# Skematik_FC.net
KiCad netlist of a schematic drawn in EAGLE
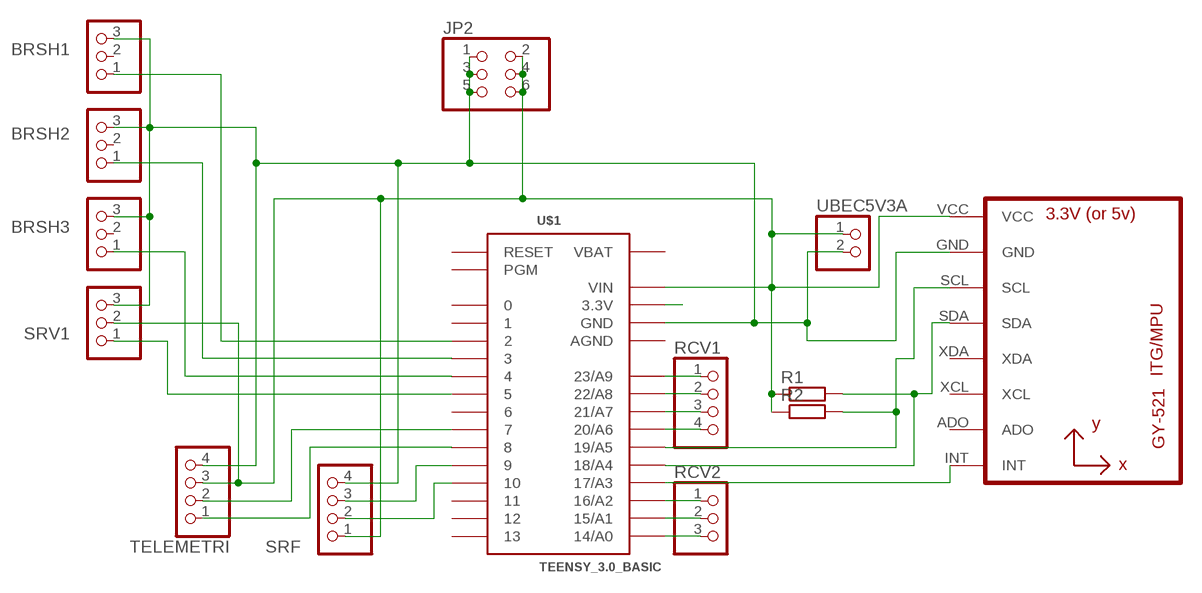
[diagram p0: schematic, sheet 1]

(export (version "E")
  (design (tool "Eeschema 10.0.6"))
  (components
    (comp (ref "BRSH1")
      (value "PINHD-1X3")
      (footprint "eagle-import:1X03")
      (libsource (lib "eagle-import") (part "PINHD-1X3"))
    )
    (comp (ref "BRSH3")
      (value "PINHD-1X3")
      (footprint "eagle-import:1X03")
      (libsource (lib "eagle-import") (part "PINHD-1X3"))
    )
    (comp (ref "BRSHL2")
      (value "BRSH2")
      (footprint "eagle-import:1X03")
      (libsource (lib "eagle-import") (part "PINHD-1X3"))
    )
    (comp (ref "JP2")
      (value "PINHD-2X3")
      (footprint "eagle-import:2X03")
      (libsource (lib "eagle-import") (part "PINHD-2X3"))
    )
    (comp (ref "R1")
      (value "R-EU_0207/7")
      (footprint "eagle-import:0207_7")
      (libsource (lib "eagle-import") (part "R-EU_0207/7"))
    )
    (comp (ref "R2")
      (value "R-EU_0207/7")
      (footprint "eagle-import:0207_7")
      (libsource (lib "eagle-import") (part "R-EU_0207/7"))
    )
    (comp (ref "RCV1")
      (value "PINHD-1X4")
      (footprint "eagle-import:1X04")
      (libsource (lib "eagle-import") (part "PINHD-1X4"))
    )
    (comp (ref "RCV2")
      (value "PINHD-1X3")
      (footprint "eagle-import:1X03")
      (libsource (lib "eagle-import") (part "PINHD-1X3"))
    )
    (comp (ref "SRF")
      (value "PINHD-1X4")
      (footprint "eagle-import:1X04")
      (libsource (lib "eagle-import") (part "PINHD-1X4"))
    )
    (comp (ref "SRV1")
      (value "PINHD-1X3")
      (footprint "eagle-import:1X03")
      (libsource (lib "eagle-import") (part "PINHD-1X3"))
    )
    (comp (ref "TELEMETRI")
      (value "PINHD-1X4")
      (footprint "eagle-import:1X04")
      (libsource (lib "eagle-import") (part "PINHD-1X4"))
    )
    (comp (ref "U$1")
      (value "TEENSY_3.0_BASIC")
      (footprint "eagle-import:TEENSY_3.0_BASIC")
      (libsource (lib "eagle-import") (part "TEENSY_3.0_BASIC"))
    )
    (comp (ref "U1")
      (value "GY-521MPU6050")
      (footprint "eagle-import:GY-521")
      (libsource (lib "eagle-import") (part "GY-521MPU6050"))
    )
    (comp (ref "UBEC5V3A")
      (value "PINHD-1X2")
      (footprint "eagle-import:1X02")
      (libsource (lib "eagle-import") (part "PINHD-1X2"))
    )
  )
  (nets
    (net (code "1") (name "/AGND") (class "Default")
      (node (ref "U$1") (pin "AGND") (pinfunction "AGND_AGND") (pintype "power_in"))
    )
    (net (code "2") (name "/VBAT") (class "Default")
      (node (ref "U$1") (pin "VBAT") (pinfunction "VBAT_VBAT") (pintype "power_in"))
    )
    (net (code "3") (name "Net-(BRSH1-Pad1)") (class "Default")
      (node (ref "BRSH1") (pin "1") (pinfunction "1_1") (pintype "passive"))
      (node (ref "U$1") (pin "2") (pinfunction "2_2") (pintype "bidirectional"))
    )
    (net (code "4") (name "Net-(BRSH1-Pad3)") (class "Default")
      (node (ref "BRSH1") (pin "3") (pinfunction "3_3") (pintype "passive"))
      (node (ref "BRSH3") (pin "3") (pinfunction "3_3") (pintype "passive"))
      (node (ref "BRSHL2") (pin "3") (pinfunction "3_3") (pintype "passive"))
      (node (ref "JP2") (pin "1") (pinfunction "1_1") (pintype "passive"))
      (node (ref "JP2") (pin "3") (pinfunction "3_3") (pintype "passive"))
      (node (ref "JP2") (pin "5") (pinfunction "5_5") (pintype "passive"))
      (node (ref "SRF") (pin "4") (pinfunction "4_4") (pintype "passive"))
      (node (ref "SRV1") (pin "3") (pinfunction "3_3") (pintype "passive"))
      (node (ref "TELEMETRI") (pin "4") (pinfunction "4_4") (pintype "passive"))
      (node (ref "U$1") (pin "GND") (pinfunction "GND_GND") (pintype "power_in"))
      (node (ref "U$1") (pin "GND1") (pinfunction "GND_GND1") (pintype "power_in"))
      (node (ref "U1") (pin "GND") (pinfunction "GND_GND") (pintype "bidirectional"))
      (node (ref "UBEC5V3A") (pin "2") (pinfunction "2_2") (pintype "passive"))
    )
    (net (code "5") (name "Net-(BRSH3-Pad1)") (class "Default")
      (node (ref "BRSH3") (pin "1") (pinfunction "1_1") (pintype "passive"))
      (node (ref "U$1") (pin "4") (pinfunction "4_4") (pintype "bidirectional"))
    )
    (net (code "6") (name "Net-(BRSHL2-Pad1)") (class "Default")
      (node (ref "BRSHL2") (pin "1") (pinfunction "1_1") (pintype "passive"))
      (node (ref "U$1") (pin "3") (pinfunction "3_3") (pintype "bidirectional"))
    )
    (net (code "7") (name "Net-(JP2-Pad2)") (class "Default")
      (node (ref "JP2") (pin "2") (pinfunction "2_2") (pintype "passive"))
      (node (ref "JP2") (pin "4") (pinfunction "4_4") (pintype "passive"))
      (node (ref "JP2") (pin "6") (pinfunction "6_6") (pintype "passive"))
      (node (ref "R1") (pin "1") (pinfunction "1_1") (pintype "passive"))
      (node (ref "R2") (pin "1") (pinfunction "1_1") (pintype "passive"))
      (node (ref "SRF") (pin "1") (pinfunction "1_1") (pintype "passive"))
      (node (ref "SRV1") (pin "2") (pinfunction "2_2") (pintype "passive"))
      (node (ref "TELEMETRI") (pin "3") (pinfunction "3_3") (pintype "passive"))
      (node (ref "U$1") (pin "VIN") (pinfunction "VIN_VIN") (pintype "power_in"))
      (node (ref "U1") (pin "VCC") (pinfunction "VCC_VCC") (pintype "bidirectional"))
      (node (ref "UBEC5V3A") (pin "1") (pinfunction "1_1") (pintype "passive"))
    )
    (net (code "8") (name "Net-(R1-Pad2)") (class "Default")
      (node (ref "R1") (pin "2") (pinfunction "2_2") (pintype "passive"))
      (node (ref "U$1") (pin "18/A4") (pinfunction "18/A4_18/A4") (pintype "bidirectional"))
      (node (ref "U1") (pin "SDA") (pinfunction "SDA_SDA") (pintype "bidirectional"))
    )
    (net (code "9") (name "Net-(R2-Pad2)") (class "Default")
      (node (ref "R2") (pin "2") (pinfunction "2_2") (pintype "passive"))
      (node (ref "U$1") (pin "19/A5") (pinfunction "19/A5_19/A5") (pintype "bidirectional"))
      (node (ref "U1") (pin "SCL") (pinfunction "SCL_SCL") (pintype "bidirectional"))
    )
    (net (code "10") (name "Net-(RCV1-Pad1)") (class "Default")
      (node (ref "RCV1") (pin "1") (pinfunction "1_1") (pintype "passive"))
      (node (ref "U$1") (pin "23/A9") (pinfunction "23/A9_23/A9") (pintype "bidirectional"))
    )
    (net (code "11") (name "Net-(RCV1-Pad2)") (class "Default")
      (node (ref "RCV1") (pin "2") (pinfunction "2_2") (pintype "passive"))
      (node (ref "U$1") (pin "22/A8") (pinfunction "22/A8_22/A8") (pintype "bidirectional"))
    )
    (net (code "12") (name "Net-(RCV1-Pad3)") (class "Default")
      (node (ref "RCV1") (pin "3") (pinfunction "3_3") (pintype "passive"))
      (node (ref "U$1") (pin "21/A7") (pinfunction "21/A7_21/A7") (pintype "bidirectional"))
    )
    (net (code "13") (name "Net-(RCV1-Pad4)") (class "Default")
      (node (ref "RCV1") (pin "4") (pinfunction "4_4") (pintype "passive"))
      (node (ref "U$1") (pin "20/A6") (pinfunction "20/A6_20/A6") (pintype "bidirectional"))
    )
    (net (code "14") (name "Net-(RCV2-Pad1)") (class "Default")
      (node (ref "RCV2") (pin "1") (pinfunction "1_1") (pintype "passive"))
      (node (ref "U$1") (pin "16/A2") (pinfunction "16/A2_16/A2") (pintype "bidirectional"))
    )
    (net (code "15") (name "Net-(RCV2-Pad2)") (class "Default")
      (node (ref "RCV2") (pin "2") (pinfunction "2_2") (pintype "passive"))
      (node (ref "U$1") (pin "15/A1") (pinfunction "15/A1_15/A1") (pintype "bidirectional"))
    )
    (net (code "16") (name "Net-(RCV2-Pad3)") (class "Default")
      (node (ref "RCV2") (pin "3") (pinfunction "3_3") (pintype "passive"))
      (node (ref "U$1") (pin "14/A0") (pinfunction "14/A0_14/A0") (pintype "bidirectional"))
    )
    (net (code "17") (name "Net-(SRF-Pad2)") (class "Default")
      (node (ref "SRF") (pin "2") (pinfunction "2_2") (pintype "passive"))
      (node (ref "U$1") (pin "10") (pinfunction "10_10") (pintype "bidirectional"))
    )
    (net (code "18") (name "Net-(SRF-Pad3)") (class "Default")
      (node (ref "SRF") (pin "3") (pinfunction "3_3") (pintype "passive"))
      (node (ref "U$1") (pin "9") (pinfunction "9_9") (pintype "bidirectional"))
    )
    (net (code "19") (name "Net-(SRV1-Pad1)") (class "Default")
      (node (ref "SRV1") (pin "1") (pinfunction "1_1") (pintype "passive"))
      (node (ref "U$1") (pin "5") (pinfunction "5_5") (pintype "bidirectional"))
    )
    (net (code "20") (name "Net-(TELEMETRI-Pad1)") (class "Default")
      (node (ref "TELEMETRI") (pin "1") (pinfunction "1_1") (pintype "passive"))
      (node (ref "U$1") (pin "8") (pinfunction "8_8") (pintype "bidirectional"))
    )
    (net (code "21") (name "Net-(TELEMETRI-Pad2)") (class "Default")
      (node (ref "TELEMETRI") (pin "2") (pinfunction "2_2") (pintype "passive"))
      (node (ref "U$1") (pin "7") (pinfunction "7_7") (pintype "bidirectional"))
    )
    (net (code "22") (name "Net-(U$1-3.3V-Pad3.3V1)") (class "Default")
      (node (ref "U$1") (pin "3.3V") (pinfunction "3.3V_3.3V") (pintype "power_in"))
      (node (ref "U$1") (pin "3.3V1") (pinfunction "3.3V_3.3V1") (pintype "power_in"))
    )
    (net (code "23") (name "Net-(U$1-Pad17{slash}A3)") (class "Default")
      (node (ref "U$1") (pin "17/A3") (pinfunction "17/A3_17/A3") (pintype "bidirectional"))
      (node (ref "U1") (pin "INT") (pinfunction "INT_INT") (pintype "bidirectional"))
    )
    (net (code "24") (name "unconnected-(BRSH1-Pad2)") (class "Default")
      (node (ref "BRSH1") (pin "2") (pinfunction "2_2") (pintype "passive"))
    )
    (net (code "25") (name "unconnected-(BRSH3-Pad2)") (class "Default")
      (node (ref "BRSH3") (pin "2") (pinfunction "2_2") (pintype "passive"))
    )
    (net (code "26") (name "unconnected-(BRSHL2-Pad2)") (class "Default")
      (node (ref "BRSHL2") (pin "2") (pinfunction "2_2") (pintype "passive"))
    )
    (net (code "27") (name "unconnected-(U$1-Pad0)") (class "Default")
      (node (ref "U$1") (pin "0") (pinfunction "0_0") (pintype "bidirectional"))
    )
    (net (code "28") (name "unconnected-(U$1-Pad1)") (class "Default")
      (node (ref "U$1") (pin "1") (pinfunction "1_1") (pintype "bidirectional"))
    )
    (net (code "29") (name "unconnected-(U$1-Pad6)") (class "Default")
      (node (ref "U$1") (pin "6") (pinfunction "6_6") (pintype "bidirectional"))
    )
    (net (code "30") (name "unconnected-(U$1-Pad11)") (class "Default")
      (node (ref "U$1") (pin "11") (pinfunction "11_11") (pintype "bidirectional"))
    )
    (net (code "31") (name "unconnected-(U$1-Pad12)") (class "Default")
      (node (ref "U$1") (pin "12") (pinfunction "12_12") (pintype "bidirectional"))
    )
    (net (code "32") (name "unconnected-(U$1-Pad13)") (class "Default")
      (node (ref "U$1") (pin "13") (pinfunction "13_13") (pintype "bidirectional"))
    )
    (net (code "33") (name "unconnected-(U$1-PadPGM)") (class "Default")
      (node (ref "U$1") (pin "PGM") (pinfunction "PGM_PGM") (pintype "bidirectional"))
    )
    (net (code "34") (name "unconnected-(U$1-PadRESET)") (class "Default")
      (node (ref "U$1") (pin "RESET") (pinfunction "RESET_RESET") (pintype "bidirectional"))
    )
    (net (code "35") (name "unconnected-(U1-PadADO)") (class "Default")
      (node (ref "U1") (pin "ADO") (pinfunction "ADO_ADO") (pintype "bidirectional"))
    )
    (net (code "36") (name "unconnected-(U1-PadXCL)") (class "Default")
      (node (ref "U1") (pin "XCL") (pinfunction "XCL_XCL") (pintype "bidirectional"))
    )
    (net (code "37") (name "unconnected-(U1-PadXDA)") (class "Default")
      (node (ref "U1") (pin "XDA") (pinfunction "XDA_XDA") (pintype "bidirectional"))
    )
  )
)
